# M226A.net
KiCad netlist of a schematic drawn in EAGLE
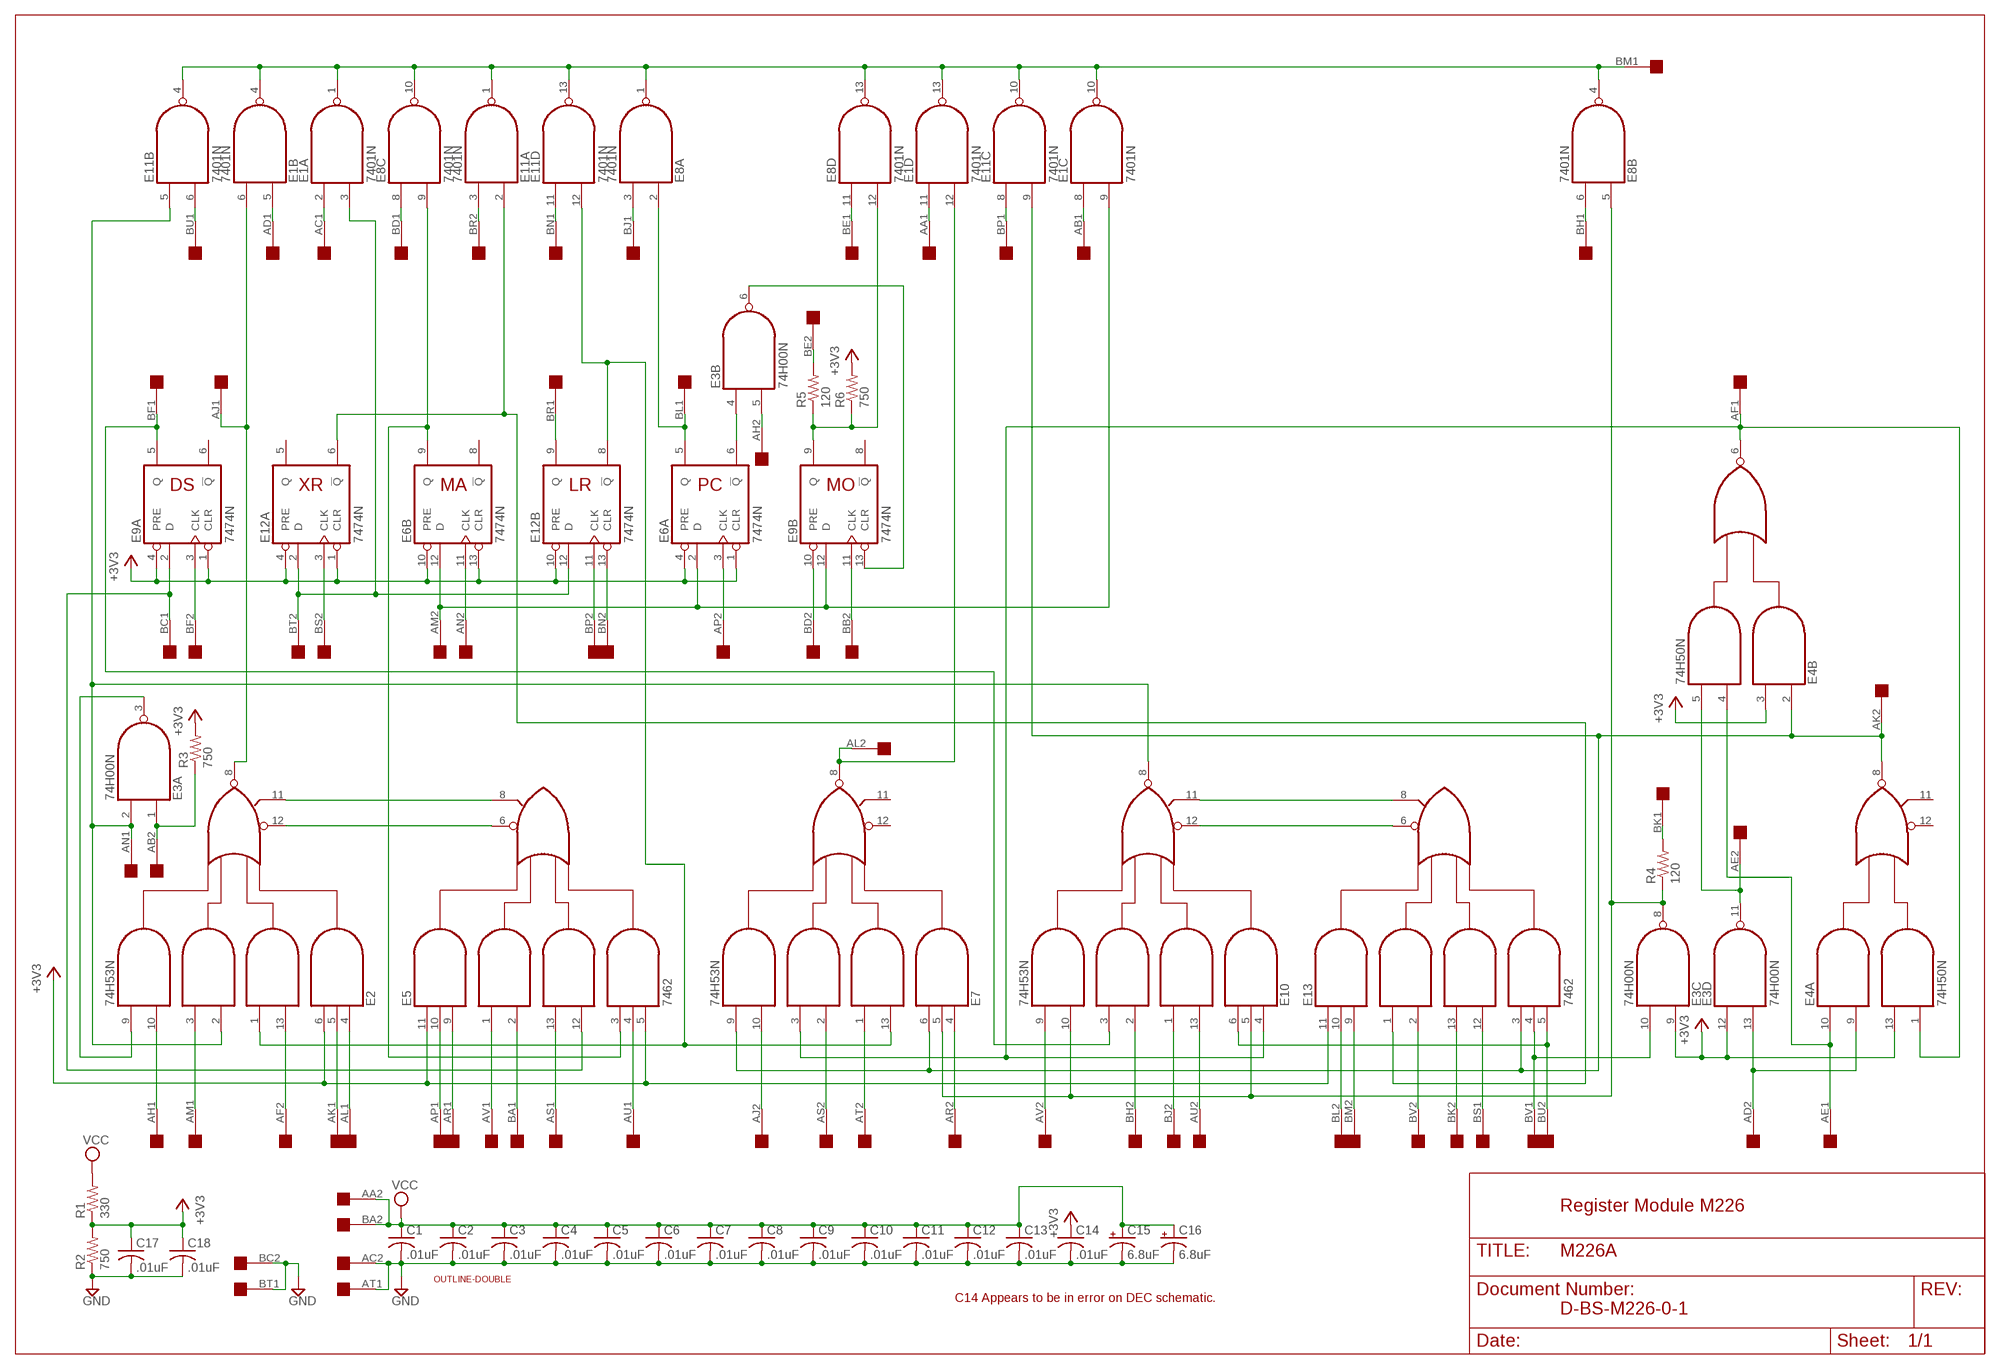
[diagram p0: schematic, sheet 1]

(export (version "E")
  (design (tool "Eeschema 10.0.6"))
  (components
    (comp (ref "C1")
      (value ".01uF")
      (footprint "eagle-import:C050-025X075")
      (libsource (lib "eagle-import") (part "C-US050-025X075"))
    )
    (comp (ref "C2")
      (value ".01uF")
      (footprint "eagle-import:C050-025X075")
      (libsource (lib "eagle-import") (part "C-US050-025X075"))
    )
    (comp (ref "C3")
      (value ".01uF")
      (footprint "eagle-import:C050-025X075")
      (libsource (lib "eagle-import") (part "C-US050-025X075"))
    )
    (comp (ref "C4")
      (value ".01uF")
      (footprint "eagle-import:C050-025X075")
      (libsource (lib "eagle-import") (part "C-US050-025X075"))
    )
    (comp (ref "C5")
      (value ".01uF")
      (footprint "eagle-import:C050-025X075")
      (libsource (lib "eagle-import") (part "C-US050-025X075"))
    )
    (comp (ref "C6")
      (value ".01uF")
      (footprint "eagle-import:C050-025X075")
      (libsource (lib "eagle-import") (part "C-US050-025X075"))
    )
    (comp (ref "C7")
      (value ".01uF")
      (footprint "eagle-import:C050-025X075")
      (libsource (lib "eagle-import") (part "C-US050-025X075"))
    )
    (comp (ref "C8")
      (value ".01uF")
      (footprint "eagle-import:C050-025X075")
      (libsource (lib "eagle-import") (part "C-US050-025X075"))
    )
    (comp (ref "C9")
      (value ".01uF")
      (footprint "eagle-import:C050-025X075")
      (libsource (lib "eagle-import") (part "C-US050-025X075"))
    )
    (comp (ref "C10")
      (value ".01uF")
      (footprint "eagle-import:C050-025X075")
      (libsource (lib "eagle-import") (part "C-US050-025X075"))
    )
    (comp (ref "C11")
      (value ".01uF")
      (footprint "eagle-import:C050-025X075")
      (libsource (lib "eagle-import") (part "C-US050-025X075"))
    )
    (comp (ref "C12")
      (value ".01uF")
      (footprint "eagle-import:C050-025X075")
      (libsource (lib "eagle-import") (part "C-US050-025X075"))
    )
    (comp (ref "C13")
      (value ".01uF")
      (footprint "eagle-import:C050-025X075")
      (libsource (lib "eagle-import") (part "C-US050-025X075"))
    )
    (comp (ref "C14")
      (value ".01uF")
      (footprint "eagle-import:C050-025X075")
      (libsource (lib "eagle-import") (part "C-US050-025X075"))
    )
    (comp (ref "C15")
      (value "6.8uF")
      (footprint "eagle-import:E12-8")
      (libsource (lib "eagle-import") (part "CPOL-USE20-8AXIAL"))
    )
    (comp (ref "C16")
      (value "6.8uF")
      (footprint "eagle-import:E12-8")
      (libsource (lib "eagle-import") (part "CPOL-USE20-8AXIAL"))
    )
    (comp (ref "C17")
      (value ".01uF")
      (footprint "eagle-import:C050-025X075")
      (libsource (lib "eagle-import") (part "C-US050-025X075"))
    )
    (comp (ref "C18")
      (value ".01uF")
      (footprint "eagle-import:C050-025X075")
      (libsource (lib "eagle-import") (part "C-US050-025X075"))
    )
    (comp (ref "E1")
      (value "7401N")
      (footprint "eagle-import:DIL14")
      (libsource (lib "eagle-import") (part "7401NLS"))
    )
    (comp (ref "E2")
      (value "74H53N")
      (footprint "eagle-import:DIL14")
      (libsource (lib "eagle-import") (part "74H53N"))
    )
    (comp (ref "E3")
      (value "74H00N")
      (footprint "eagle-import:DIL14")
      (libsource (lib "eagle-import") (part "7400NS"))
    )
    (comp (ref "E4")
      (value "74H50N")
      (footprint "eagle-import:DIL14")
      (libsource (lib "eagle-import") (part "7450N"))
    )
    (comp (ref "E5")
      (value "7462")
      (footprint "eagle-import:DIL14")
      (libsource (lib "eagle-import") (part "7462"))
    )
    (comp (ref "E6")
      (value "7474N")
      (footprint "eagle-import:DIL14")
      (libsource (lib "eagle-import") (part "7474NS"))
    )
    (comp (ref "E7")
      (value "74H53N")
      (footprint "eagle-import:DIL14")
      (libsource (lib "eagle-import") (part "74H53N"))
    )
    (comp (ref "E8")
      (value "7401N")
      (footprint "eagle-import:DIL14")
      (libsource (lib "eagle-import") (part "7401NLS"))
    )
    (comp (ref "E9")
      (value "7474N")
      (footprint "eagle-import:DIL14")
      (libsource (lib "eagle-import") (part "7474NS"))
    )
    (comp (ref "E10")
      (value "74H53N")
      (footprint "eagle-import:DIL14")
      (libsource (lib "eagle-import") (part "74H53N"))
    )
    (comp (ref "E11")
      (value "7401N")
      (footprint "eagle-import:DIL14")
      (libsource (lib "eagle-import") (part "7401NLS"))
    )
    (comp (ref "E12")
      (value "7474N")
      (footprint "eagle-import:DIL14")
      (libsource (lib "eagle-import") (part "7474NS"))
    )
    (comp (ref "E13")
      (value "7462")
      (footprint "eagle-import:DIL14")
      (libsource (lib "eagle-import") (part "7462"))
    )
    (comp (ref "R1")
      (value "330")
      (footprint "eagle-import:0207_10")
      (libsource (lib "eagle-import") (part "R-US_0207/10"))
    )
    (comp (ref "R2")
      (value "750")
      (footprint "eagle-import:0207_10")
      (libsource (lib "eagle-import") (part "R-US_0207/10"))
    )
    (comp (ref "R3")
      (value "750")
      (footprint "eagle-import:0207_10")
      (libsource (lib "eagle-import") (part "R-US_0207/10"))
    )
    (comp (ref "R4")
      (value "120")
      (footprint "eagle-import:0207_10")
      (libsource (lib "eagle-import") (part "R-US_0207/10"))
    )
    (comp (ref "R5")
      (value "120")
      (footprint "eagle-import:0207_10")
      (libsource (lib "eagle-import") (part "R-US_0207/10"))
    )
    (comp (ref "R6")
      (value "750")
      (footprint "eagle-import:0207_10")
      (libsource (lib "eagle-import") (part "R-US_0207/10"))
    )
    (comp (ref "U$1")
      (value "OUTLINE-DOUBLE")
      (footprint "eagle-import:DOUBLE")
      (libsource (lib "eagle-import") (part "OUTLINE-DOUBLE"))
    )
    (comp (ref "U$3")
      (value "DOUBLE")
      (footprint "eagle-import:EDGE-CON4")
      (libsource (lib "eagle-import") (part "DOUBLE"))
    )
  )
  (nets
    (net (code "1") (name "+3V3") (class "Default")
      (node (ref "C14") (pin "1") (pinfunction "1_1") (pintype "passive"))
      (node (ref "C17") (pin "1") (pinfunction "1_1") (pintype "passive"))
      (node (ref "C18") (pin "1") (pinfunction "1_1") (pintype "passive"))
      (node (ref "E12") (pin "1") (pinfunction "CLR_1") (pintype "input"))
      (node (ref "E12") (pin "10") (pinfunction "PRE_10") (pintype "input"))
      (node (ref "E12") (pin "4") (pinfunction "PRE_4") (pintype "input"))
      (node (ref "E13") (pin "11") (pinfunction "I1_11") (pintype "input"))
      (node (ref "E2") (pin "6") (pinfunction "I2_6") (pintype "input"))
      (node (ref "E3") (pin "12") (pinfunction "I0_12") (pintype "input"))
      (node (ref "E3") (pin "9") (pinfunction "I0_9") (pintype "input"))
      (node (ref "E4") (pin "13") (pinfunction "I3_13") (pintype "input"))
      (node (ref "E4") (pin "3") (pinfunction "I2_3") (pintype "input"))
      (node (ref "E5") (pin "11") (pinfunction "I1_11") (pintype "input"))
      (node (ref "E5") (pin "5") (pinfunction "I10_5") (pintype "input"))
      (node (ref "E6") (pin "1") (pinfunction "CLR_1") (pintype "input"))
      (node (ref "E6") (pin "10") (pinfunction "PRE_10") (pintype "input"))
      (node (ref "E6") (pin "13") (pinfunction "CLR_13") (pintype "input"))
      (node (ref "E6") (pin "4") (pinfunction "PRE_4") (pintype "input"))
      (node (ref "E9") (pin "1") (pinfunction "CLR_1") (pintype "input"))
      (node (ref "E9") (pin "4") (pinfunction "PRE_4") (pintype "input"))
      (node (ref "R1") (pin "1") (pinfunction "1_1") (pintype "passive"))
      (node (ref "R2") (pin "2") (pinfunction "2_2") (pintype "passive"))
      (node (ref "R3") (pin "2") (pinfunction "2_2") (pintype "passive"))
      (node (ref "R6") (pin "2") (pinfunction "2_2") (pintype "passive"))
    )
    (net (code "2") (name "GND") (class "Default")
      (node (ref "C1") (pin "2") (pinfunction "2_2") (pintype "passive"))
      (node (ref "C10") (pin "2") (pinfunction "2_2") (pintype "passive"))
      (node (ref "C11") (pin "2") (pinfunction "2_2") (pintype "passive"))
      (node (ref "C12") (pin "2") (pinfunction "2_2") (pintype "passive"))
      (node (ref "C13") (pin "2") (pinfunction "2_2") (pintype "passive"))
      (node (ref "C14") (pin "2") (pinfunction "2_2") (pintype "passive"))
      (node (ref "C15") (pin "-") (pinfunction "-_-") (pintype "passive"))
      (node (ref "C16") (pin "-") (pinfunction "-_-") (pintype "passive"))
      (node (ref "C17") (pin "2") (pinfunction "2_2") (pintype "passive"))
      (node (ref "C18") (pin "2") (pinfunction "2_2") (pintype "passive"))
      (node (ref "C2") (pin "2") (pinfunction "2_2") (pintype "passive"))
      (node (ref "C3") (pin "2") (pinfunction "2_2") (pintype "passive"))
      (node (ref "C4") (pin "2") (pinfunction "2_2") (pintype "passive"))
      (node (ref "C5") (pin "2") (pinfunction "2_2") (pintype "passive"))
      (node (ref "C6") (pin "2") (pinfunction "2_2") (pintype "passive"))
      (node (ref "C7") (pin "2") (pinfunction "2_2") (pintype "passive"))
      (node (ref "C8") (pin "2") (pinfunction "2_2") (pintype "passive"))
      (node (ref "C9") (pin "2") (pinfunction "2_2") (pintype "passive"))
      (node (ref "R2") (pin "1") (pinfunction "1_1") (pintype "passive"))
      (node (ref "U$3") (pin "AC2") (pinfunction "1_AC2") (pintype "bidirectional"))
      (node (ref "U$3") (pin "AT1") (pinfunction "1_AT1") (pintype "bidirectional"))
      (node (ref "U$3") (pin "BC2") (pinfunction "1_BC2") (pintype "bidirectional"))
      (node (ref "U$3") (pin "BT1") (pinfunction "1_BT1") (pintype "bidirectional"))
    )
    (net (code "3") (name "Net-(E1A-I0)") (class "Default")
      (node (ref "E1") (pin "2") (pinfunction "I0_2") (pintype "input"))
      (node (ref "U$3") (pin "AC1") (pinfunction "1_AC1") (pintype "bidirectional"))
    )
    (net (code "4") (name "Net-(E1B-I0)") (class "Default")
      (node (ref "E1") (pin "5") (pinfunction "I0_5") (pintype "input"))
      (node (ref "U$3") (pin "AD1") (pinfunction "1_AD1") (pintype "bidirectional"))
    )
    (net (code "5") (name "Net-(E1B-I1)") (class "Default")
      (node (ref "E1") (pin "6") (pinfunction "I1_6") (pintype "input"))
      (node (ref "E2") (pin "8") (pinfunction "O_8") (pintype "output"))
      (node (ref "U$3") (pin "AJ1") (pinfunction "1_AJ1") (pintype "bidirectional"))
    )
    (net (code "6") (name "Net-(E1C-I0)") (class "Default")
      (node (ref "E1") (pin "8") (pinfunction "I0_8") (pintype "input"))
      (node (ref "U$3") (pin "AB1") (pinfunction "1_AB1") (pintype "bidirectional"))
    )
    (net (code "7") (name "Net-(E1C-I1)") (class "Default")
      (node (ref "E1") (pin "9") (pinfunction "I1_9") (pintype "input"))
      (node (ref "E6") (pin "12") (pinfunction "D_12") (pintype "input"))
      (node (ref "E6") (pin "2") (pinfunction "D_2") (pintype "input"))
      (node (ref "E9") (pin "12") (pinfunction "D_12") (pintype "input"))
      (node (ref "U$3") (pin "AM2") (pinfunction "1_AM2") (pintype "bidirectional"))
    )
    (net (code "8") (name "Net-(E1D-I0)") (class "Default")
      (node (ref "E1") (pin "11") (pinfunction "I0_11") (pintype "input"))
      (node (ref "U$3") (pin "AA1") (pinfunction "1_AA1") (pintype "bidirectional"))
    )
    (net (code "9") (name "Net-(E1D-I1)") (class "Default")
      (node (ref "E1") (pin "12") (pinfunction "I1_12") (pintype "input"))
      (node (ref "E7") (pin "8") (pinfunction "O_8") (pintype "output"))
      (node (ref "U$3") (pin "AL2") (pinfunction "1_AL2") (pintype "bidirectional"))
    )
    (net (code "10") (name "Net-(E2A-I1)") (class "Default")
      (node (ref "E2") (pin "4") (pinfunction "I1_4") (pintype "input"))
      (node (ref "U$3") (pin "AL1") (pinfunction "1_AL1") (pintype "bidirectional"))
    )
    (net (code "11") (name "Net-(E2A-I3)") (class "Default")
      (node (ref "E2") (pin "13") (pinfunction "I3_13") (pintype "input"))
      (node (ref "U$3") (pin "AF2") (pinfunction "1_AF2") (pintype "bidirectional"))
    )
    (net (code "12") (name "Net-(E2A-I6)") (class "Default")
      (node (ref "E2") (pin "3") (pinfunction "I6_3") (pintype "input"))
      (node (ref "U$3") (pin "AM1") (pinfunction "1_AM1") (pintype "bidirectional"))
    )
    (net (code "13") (name "Net-(E2A-I7)") (class "Default")
      (node (ref "E2") (pin "10") (pinfunction "I7_10") (pintype "input"))
      (node (ref "U$3") (pin "AH1") (pinfunction "1_AH1") (pintype "bidirectional"))
    )
    (net (code "14") (name "Net-(E2A-I8)") (class "Default")
      (node (ref "E2") (pin "9") (pinfunction "I8_9") (pintype "input"))
      (node (ref "E3") (pin "3") (pinfunction "O_3") (pintype "output"))
    )
    (net (code "15") (name "Net-(E2A-I9)") (class "Default")
      (node (ref "E2") (pin "12") (pinfunction "I9_12") (pintype "passive"))
      (node (ref "E5") (pin "6") (pinfunction "E0_6") (pintype "passive"))
    )
    (net (code "16") (name "Net-(E2A-I10)") (class "Default")
      (node (ref "E2") (pin "11") (pinfunction "I10_11") (pintype "passive"))
      (node (ref "E5") (pin "8") (pinfunction "E1_8") (pintype "passive"))
    )
    (net (code "17") (name "Net-(E2A-I11)") (class "Default")
      (node (ref "E2") (pin "5") (pinfunction "I11_5") (pintype "input"))
      (node (ref "U$3") (pin "AK1") (pinfunction "1_AK1") (pintype "bidirectional"))
    )
    (net (code "18") (name "Net-(E3A-I0)") (class "Default")
      (node (ref "E3") (pin "1") (pinfunction "I0_1") (pintype "input"))
      (node (ref "R3") (pin "1") (pinfunction "1_1") (pintype "passive"))
      (node (ref "U$3") (pin "AB2") (pinfunction "1_AB2") (pintype "bidirectional"))
    )
    (net (code "19") (name "Net-(E3B-I0)") (class "Default")
      (node (ref "E3") (pin "4") (pinfunction "I0_4") (pintype "input"))
      (node (ref "E6") (pin "6") (pinfunction "~{Q}_6") (pintype "output"))
    )
    (net (code "20") (name "Net-(E3B-I1)") (class "Default")
      (node (ref "E3") (pin "5") (pinfunction "I1_5") (pintype "input"))
      (node (ref "U$3") (pin "AH2") (pinfunction "1_AH2") (pintype "bidirectional"))
    )
    (net (code "21") (name "Net-(E3B-O)") (class "Default")
      (node (ref "E3") (pin "6") (pinfunction "O_6") (pintype "output"))
      (node (ref "E9") (pin "13") (pinfunction "CLR_13") (pintype "input"))
    )
    (net (code "22") (name "Net-(E3D-I1)") (class "Default")
      (node (ref "E3") (pin "13") (pinfunction "I1_13") (pintype "input"))
      (node (ref "E4") (pin "9") (pinfunction "I2_9") (pintype "input"))
      (node (ref "U$3") (pin "AD2") (pinfunction "1_AD2") (pintype "bidirectional"))
    )
    (net (code "23") (name "Net-(E3D-O)") (class "Default")
      (node (ref "E3") (pin "11") (pinfunction "O_11") (pintype "output"))
      (node (ref "E4") (pin "5") (pinfunction "I4_5") (pintype "input"))
      (node (ref "U$3") (pin "AE2") (pinfunction "1_AE2") (pintype "bidirectional"))
    )
    (net (code "24") (name "Net-(E4A-I1)") (class "Default")
      (node (ref "E4") (pin "10") (pinfunction "I1_10") (pintype "input"))
      (node (ref "E4") (pin "4") (pinfunction "I3_4") (pintype "input"))
      (node (ref "U$3") (pin "AE1") (pinfunction "1_AE1") (pintype "bidirectional"))
    )
    (net (code "25") (name "Net-(E5A-I2)") (class "Default")
      (node (ref "E5") (pin "10") (pinfunction "I2_10") (pintype "input"))
      (node (ref "U$3") (pin "AP1") (pinfunction "1_AP1") (pintype "bidirectional"))
    )
    (net (code "26") (name "Net-(E5A-I3)") (class "Default")
      (node (ref "E5") (pin "9") (pinfunction "I3_9") (pintype "input"))
      (node (ref "U$3") (pin "AR1") (pinfunction "1_AR1") (pintype "bidirectional"))
    )
    (net (code "27") (name "Net-(E5A-I4)") (class "Default")
      (node (ref "E5") (pin "1") (pinfunction "I4_1") (pintype "input"))
      (node (ref "U$3") (pin "AV1") (pinfunction "1_AV1") (pintype "bidirectional"))
    )
    (net (code "28") (name "Net-(E5A-I5)") (class "Default")
      (node (ref "E5") (pin "2") (pinfunction "I5_2") (pintype "input"))
      (node (ref "U$3") (pin "BA1") (pinfunction "1_BA1") (pintype "bidirectional"))
    )
    (net (code "29") (name "Net-(E5A-I6)") (class "Default")
      (node (ref "E5") (pin "13") (pinfunction "I6_13") (pintype "input"))
      (node (ref "U$3") (pin "AS1") (pinfunction "1_AS1") (pintype "bidirectional"))
    )
    (net (code "30") (name "Net-(E5A-I7)") (class "Default")
      (node (ref "E5") (pin "12") (pinfunction "I7_12") (pintype "input"))
      (node (ref "E9") (pin "2") (pinfunction "D_2") (pintype "input"))
      (node (ref "U$3") (pin "BC1") (pinfunction "1_BC1") (pintype "bidirectional"))
    )
    (net (code "31") (name "Net-(E5A-I8)") (class "Default")
      (node (ref "E5") (pin "3") (pinfunction "I8_3") (pintype "input"))
      (node (ref "E6") (pin "9") (pinfunction "Q_9") (pintype "output"))
      (node (ref "E8") (pin "9") (pinfunction "I1_9") (pintype "input"))
    )
    (net (code "32") (name "Net-(E5A-I9)") (class "Default")
      (node (ref "E5") (pin "4") (pinfunction "I9_4") (pintype "input"))
      (node (ref "U$3") (pin "AU1") (pinfunction "1_AU1") (pintype "bidirectional"))
    )
    (net (code "33") (name "Net-(E6A-CLK)") (class "Default")
      (node (ref "E6") (pin "3") (pinfunction "CLK_3") (pintype "input"))
      (node (ref "U$3") (pin "AP2") (pinfunction "1_AP2") (pintype "bidirectional"))
    )
    (net (code "34") (name "Net-(E6A-Q)") (class "Default")
      (node (ref "E6") (pin "5") (pinfunction "Q_5") (pintype "output"))
      (node (ref "E8") (pin "2") (pinfunction "I0_2") (pintype "input"))
      (node (ref "U$3") (pin "BL1") (pinfunction "1_BL1") (pintype "bidirectional"))
    )
    (net (code "35") (name "Net-(E6B-CLK)") (class "Default")
      (node (ref "E6") (pin "11") (pinfunction "CLK_11") (pintype "input"))
      (node (ref "U$3") (pin "AN2") (pinfunction "1_AN2") (pintype "bidirectional"))
    )
    (net (code "36") (name "Net-(E7A-I1)") (class "Default")
      (node (ref "E7") (pin "4") (pinfunction "I1_4") (pintype "input"))
      (node (ref "U$3") (pin "AR2") (pinfunction "1_AR2") (pintype "bidirectional"))
    )
    (net (code "37") (name "Net-(E7A-I4)") (class "Default")
      (node (ref "E7") (pin "1") (pinfunction "I4_1") (pintype "input"))
      (node (ref "U$3") (pin "AT2") (pinfunction "1_AT2") (pintype "bidirectional"))
    )
    (net (code "38") (name "Net-(E7A-I5)") (class "Default")
      (node (ref "E7") (pin "2") (pinfunction "I5_2") (pintype "input"))
      (node (ref "U$3") (pin "AS2") (pinfunction "1_AS2") (pintype "bidirectional"))
    )
    (net (code "39") (name "Net-(E7A-I7)") (class "Default")
      (node (ref "E7") (pin "10") (pinfunction "I7_10") (pintype "input"))
      (node (ref "U$3") (pin "AJ2") (pinfunction "1_AJ2") (pintype "bidirectional"))
    )
    (net (code "40") (name "Net-(E8A-I1)") (class "Default")
      (node (ref "E8") (pin "3") (pinfunction "I1_3") (pintype "input"))
      (node (ref "U$3") (pin "BJ1") (pinfunction "1_BJ1") (pintype "bidirectional"))
    )
    (net (code "41") (name "Net-(E8B-I1)") (class "Default")
      (node (ref "E8") (pin "6") (pinfunction "I1_6") (pintype "input"))
      (node (ref "U$3") (pin "BH1") (pinfunction "1_BH1") (pintype "bidirectional"))
    )
    (net (code "42") (name "Net-(E8C-I0)") (class "Default")
      (node (ref "E8") (pin "8") (pinfunction "I0_8") (pintype "input"))
      (node (ref "U$3") (pin "BD1") (pinfunction "1_BD1") (pintype "bidirectional"))
    )
    (net (code "43") (name "Net-(E8D-I0)") (class "Default")
      (node (ref "E8") (pin "11") (pinfunction "I0_11") (pintype "input"))
      (node (ref "U$3") (pin "BE1") (pinfunction "1_BE1") (pintype "bidirectional"))
    )
    (net (code "44") (name "Net-(E8D-I1)") (class "Default")
      (node (ref "E8") (pin "12") (pinfunction "I1_12") (pintype "input"))
      (node (ref "E9") (pin "9") (pinfunction "Q_9") (pintype "output"))
      (node (ref "R5") (pin "1") (pinfunction "1_1") (pintype "passive"))
      (node (ref "R6") (pin "1") (pinfunction "1_1") (pintype "passive"))
    )
    (net (code "45") (name "Net-(E9A-CLK)") (class "Default")
      (node (ref "E9") (pin "3") (pinfunction "CLK_3") (pintype "input"))
      (node (ref "U$3") (pin "BF2") (pinfunction "1_BF2") (pintype "bidirectional"))
    )
    (net (code "46") (name "Net-(E9B-CLK)") (class "Default")
      (node (ref "E9") (pin "11") (pinfunction "CLK_11") (pintype "input"))
      (node (ref "U$3") (pin "BB2") (pinfunction "1_BB2") (pintype "bidirectional"))
    )
    (net (code "47") (name "Net-(E9B-PRE)") (class "Default")
      (node (ref "E9") (pin "10") (pinfunction "PRE_10") (pintype "input"))
      (node (ref "U$3") (pin "BD2") (pinfunction "1_BD2") (pintype "bidirectional"))
    )
    (net (code "48") (name "Net-(E10A-I1)") (class "Default")
      (node (ref "E10") (pin "4") (pinfunction "I1_4") (pintype "input"))
      (node (ref "E4") (pin "1") (pinfunction "I4_1") (pintype "input"))
      (node (ref "E4") (pin "6") (pinfunction "O_6") (pintype "output"))
      (node (ref "E7") (pin "3") (pinfunction "I6_3") (pintype "input"))
      (node (ref "U$3") (pin "AF1") (pinfunction "1_AF1") (pintype "bidirectional"))
    )
    (net (code "49") (name "Net-(E10A-I2)") (class "Default")
      (node (ref "E10") (pin "6") (pinfunction "I2_6") (pintype "input"))
      (node (ref "E13") (pin "5") (pinfunction "I10_5") (pintype "input"))
      (node (ref "U$3") (pin "BU2") (pinfunction "1_BU2") (pintype "bidirectional"))
    )
    (net (code "50") (name "Net-(E10A-I3)") (class "Default")
      (node (ref "E10") (pin "13") (pinfunction "I3_13") (pintype "input"))
      (node (ref "U$3") (pin "AU2") (pinfunction "1_AU2") (pintype "bidirectional"))
    )
    (net (code "51") (name "Net-(E10A-I4)") (class "Default")
      (node (ref "E10") (pin "1") (pinfunction "I4_1") (pintype "input"))
      (node (ref "U$3") (pin "BJ2") (pinfunction "1_BJ2") (pintype "bidirectional"))
    )
    (net (code "52") (name "Net-(E10A-I5)") (class "Default")
      (node (ref "E10") (pin "2") (pinfunction "I5_2") (pintype "input"))
      (node (ref "U$3") (pin "BH2") (pinfunction "1_BH2") (pintype "bidirectional"))
    )
    (net (code "53") (name "Net-(E10A-I6)") (class "Default")
      (node (ref "E10") (pin "3") (pinfunction "I6_3") (pintype "input"))
      (node (ref "E9") (pin "5") (pinfunction "Q_5") (pintype "output"))
      (node (ref "U$3") (pin "BF1") (pinfunction "1_BF1") (pintype "bidirectional"))
    )
    (net (code "54") (name "Net-(E10A-I8)") (class "Default")
      (node (ref "E10") (pin "9") (pinfunction "I8_9") (pintype "input"))
      (node (ref "U$3") (pin "AV2") (pinfunction "1_AV2") (pintype "bidirectional"))
    )
    (net (code "55") (name "Net-(E10A-I9)") (class "Default")
      (node (ref "E10") (pin "12") (pinfunction "I9_12") (pintype "passive"))
      (node (ref "E13") (pin "6") (pinfunction "E0_6") (pintype "passive"))
    )
    (net (code "56") (name "Net-(E10A-I10)") (class "Default")
      (node (ref "E10") (pin "11") (pinfunction "I10_11") (pintype "passive"))
      (node (ref "E13") (pin "8") (pinfunction "E1_8") (pintype "passive"))
    )
    (net (code "57") (name "Net-(E10A-I11)") (class "Default")
      (node (ref "E10") (pin "10") (pinfunction "I7_10") (pintype "input"))
      (node (ref "E10") (pin "5") (pinfunction "I11_5") (pintype "input"))
      (node (ref "E3") (pin "8") (pinfunction "O_8") (pintype "output"))
      (node (ref "E7") (pin "5") (pinfunction "I11_5") (pintype "input"))
      (node (ref "E8") (pin "5") (pinfunction "I0_5") (pintype "input"))
      (node (ref "R4") (pin "1") (pinfunction "1_1") (pintype "passive"))
    )
    (net (code "58") (name "Net-(E10A-O)") (class "Default")
      (node (ref "E10") (pin "8") (pinfunction "O_8") (pintype "output"))
      (node (ref "E11") (pin "5") (pinfunction "I0_5") (pintype "input"))
      (node (ref "E2") (pin "2") (pinfunction "I5_2") (pintype "input"))
      (node (ref "E3") (pin "2") (pinfunction "I1_2") (pintype "input"))
      (node (ref "U$3") (pin "AN1") (pinfunction "1_AN1") (pintype "bidirectional"))
    )
    (net (code "59") (name "Net-(E11A-I0)") (class "Default")
      (node (ref "E11") (pin "2") (pinfunction "I0_2") (pintype "input"))
      (node (ref "E12") (pin "6") (pinfunction "~{Q}_6") (pintype "output"))
      (node (ref "E13") (pin "1") (pinfunction "I4_1") (pintype "input"))
    )
    (net (code "60") (name "Net-(E11A-I1)") (class "Default")
      (node (ref "E11") (pin "3") (pinfunction "I1_3") (pintype "input"))
      (node (ref "U$3") (pin "BR2") (pinfunction "1_BR2") (pintype "bidirectional"))
    )
    (net (code "61") (name "Net-(E11A-O)") (class "Default")
      (node (ref "E1") (pin "1") (pinfunction "O_1") (pintype "open_collector"))
      (node (ref "E1") (pin "10") (pinfunction "O_10") (pintype "open_collector"))
      (node (ref "E1") (pin "13") (pinfunction "O_13") (pintype "open_collector"))
      (node (ref "E1") (pin "4") (pinfunction "O_4") (pintype "open_collector"))
      (node (ref "E11") (pin "1") (pinfunction "O_1") (pintype "open_collector"))
      (node (ref "E11") (pin "10") (pinfunction "O_10") (pintype "open_collector"))
      (node (ref "E11") (pin "13") (pinfunction "O_13") (pintype "open_collector"))
      (node (ref "E11") (pin "4") (pinfunction "O_4") (pintype "open_collector"))
      (node (ref "E8") (pin "1") (pinfunction "O_1") (pintype "open_collector"))
      (node (ref "E8") (pin "10") (pinfunction "O_10") (pintype "open_collector"))
      (node (ref "E8") (pin "13") (pinfunction "O_13") (pintype "open_collector"))
      (node (ref "E8") (pin "4") (pinfunction "O_4") (pintype "open_collector"))
      (node (ref "U$3") (pin "BM1") (pinfunction "1_BM1") (pintype "bidirectional"))
    )
    (net (code "62") (name "Net-(E11B-I1)") (class "Default")
      (node (ref "E11") (pin "6") (pinfunction "I1_6") (pintype "input"))
      (node (ref "U$3") (pin "BU1") (pinfunction "1_BU1") (pintype "bidirectional"))
    )
    (net (code "63") (name "Net-(E11C-I0)") (class "Default")
      (node (ref "E11") (pin "8") (pinfunction "I0_8") (pintype "input"))
      (node (ref "U$3") (pin "BP1") (pinfunction "1_BP1") (pintype "bidirectional"))
    )
    (net (code "64") (name "Net-(E11C-I1)") (class "Default")
      (node (ref "E11") (pin "9") (pinfunction "I1_9") (pintype "input"))
      (node (ref "E13") (pin "3") (pinfunction "I8_3") (pintype "input"))
      (node (ref "E4") (pin "2") (pinfunction "I1_2") (pintype "input"))
      (node (ref "E4") (pin "8") (pinfunction "O_8") (pintype "output"))
      (node (ref "E7") (pin "6") (pinfunction "I2_6") (pintype "input"))
      (node (ref "E7") (pin "9") (pinfunction "I8_9") (pintype "input"))
      (node (ref "U$3") (pin "AK2") (pinfunction "1_AK2") (pintype "bidirectional"))
    )
    (net (code "65") (name "Net-(E11D-I0)") (class "Default")
      (node (ref "E11") (pin "11") (pinfunction "I0_11") (pintype "input"))
      (node (ref "U$3") (pin "BN1") (pinfunction "1_BN1") (pintype "bidirectional"))
    )
    (net (code "66") (name "Net-(E11D-I1)") (class "Default")
      (node (ref "E11") (pin "12") (pinfunction "I1_12") (pintype "input"))
      (node (ref "E12") (pin "8") (pinfunction "~{Q}_8") (pintype "output"))
      (node (ref "E2") (pin "1") (pinfunction "I4_1") (pintype "input"))
      (node (ref "E7") (pin "13") (pinfunction "I3_13") (pintype "input"))
    )
    (net (code "67") (name "Net-(E12A-CLK)") (class "Default")
      (node (ref "E12") (pin "3") (pinfunction "CLK_3") (pintype "input"))
      (node (ref "U$3") (pin "BS2") (pinfunction "1_BS2") (pintype "bidirectional"))
    )
    (net (code "68") (name "Net-(E12A-D)") (class "Default")
      (node (ref "E1") (pin "3") (pinfunction "I1_3") (pintype "input"))
      (node (ref "E12") (pin "12") (pinfunction "D_12") (pintype "input"))
      (node (ref "E12") (pin "2") (pinfunction "D_2") (pintype "input"))
      (node (ref "U$3") (pin "BT2") (pinfunction "1_BT2") (pintype "bidirectional"))
    )
    (net (code "69") (name "Net-(E12B-CLK)") (class "Default")
      (node (ref "E12") (pin "11") (pinfunction "CLK_11") (pintype "input"))
      (node (ref "U$3") (pin "BP2") (pinfunction "1_BP2") (pintype "bidirectional"))
    )
    (net (code "70") (name "Net-(E12B-CLR)") (class "Default")
      (node (ref "E12") (pin "13") (pinfunction "CLR_13") (pintype "input"))
      (node (ref "U$3") (pin "BN2") (pinfunction "1_BN2") (pintype "bidirectional"))
    )
    (net (code "71") (name "Net-(E12B-Q)") (class "Default")
      (node (ref "E12") (pin "9") (pinfunction "Q_9") (pintype "output"))
      (node (ref "U$3") (pin "BR1") (pinfunction "1_BR1") (pintype "bidirectional"))
    )
    (net (code "72") (name "Net-(E13A-I2)") (class "Default")
      (node (ref "E13") (pin "10") (pinfunction "I2_10") (pintype "input"))
      (node (ref "U$3") (pin "BL2") (pinfunction "1_BL2") (pintype "bidirectional"))
    )
    (net (code "73") (name "Net-(E13A-I3)") (class "Default")
      (node (ref "E13") (pin "9") (pinfunction "I3_9") (pintype "input"))
      (node (ref "U$3") (pin "BM2") (pinfunction "1_BM2") (pintype "bidirectional"))
    )
    (net (code "74") (name "Net-(E13A-I5)") (class "Default")
      (node (ref "E13") (pin "2") (pinfunction "I5_2") (pintype "input"))
      (node (ref "U$3") (pin "BV2") (pinfunction "1_BV2") (pintype "bidirectional"))
    )
    (net (code "75") (name "Net-(E13A-I6)") (class "Default")
      (node (ref "E13") (pin "13") (pinfunction "I6_13") (pintype "input"))
      (node (ref "U$3") (pin "BK2") (pinfunction "1_BK2") (pintype "bidirectional"))
    )
    (net (code "76") (name "Net-(E13A-I7)") (class "Default")
      (node (ref "E13") (pin "12") (pinfunction "I7_12") (pintype "input"))
      (node (ref "U$3") (pin "BS1") (pinfunction "1_BS1") (pintype "bidirectional"))
    )
    (net (code "77") (name "Net-(E13A-I9)") (class "Default")
      (node (ref "E13") (pin "4") (pinfunction "I9_4") (pintype "input"))
      (node (ref "E3") (pin "10") (pinfunction "I1_10") (pintype "input"))
      (node (ref "U$3") (pin "BV1") (pinfunction "1_BV1") (pintype "bidirectional"))
    )
    (net (code "78") (name "Net-(U$3AT-1)") (class "Default")
      (node (ref "R5") (pin "2") (pinfunction "2_2") (pintype "passive"))
      (node (ref "U$3") (pin "BE2") (pinfunction "1_BE2") (pintype "bidirectional"))
    )
    (net (code "79") (name "Net-(U$3BA-1)") (class "Default")
      (node (ref "R4") (pin "2") (pinfunction "2_2") (pintype "passive"))
      (node (ref "U$3") (pin "BK1") (pinfunction "1_BK1") (pintype "bidirectional"))
    )
    (net (code "80") (name "VCC") (class "Default")
      (node (ref "C1") (pin "1") (pinfunction "1_1") (pintype "passive"))
      (node (ref "C10") (pin "1") (pinfunction "1_1") (pintype "passive"))
      (node (ref "C11") (pin "1") (pinfunction "1_1") (pintype "passive"))
      (node (ref "C12") (pin "1") (pinfunction "1_1") (pintype "passive"))
      (node (ref "C13") (pin "1") (pinfunction "1_1") (pintype "passive"))
      (node (ref "C15") (pin "+") (pinfunction "+_+") (pintype "passive"))
      (node (ref "C16") (pin "+") (pinfunction "+_+") (pintype "passive"))
      (node (ref "C2") (pin "1") (pinfunction "1_1") (pintype "passive"))
      (node (ref "C3") (pin "1") (pinfunction "1_1") (pintype "passive"))
      (node (ref "C4") (pin "1") (pinfunction "1_1") (pintype "passive"))
      (node (ref "C5") (pin "1") (pinfunction "1_1") (pintype "passive"))
      (node (ref "C6") (pin "1") (pinfunction "1_1") (pintype "passive"))
      (node (ref "C7") (pin "1") (pinfunction "1_1") (pintype "passive"))
      (node (ref "C8") (pin "1") (pinfunction "1_1") (pintype "passive"))
      (node (ref "C9") (pin "1") (pinfunction "1_1") (pintype "passive"))
      (node (ref "R1") (pin "2") (pinfunction "2_2") (pintype "passive"))
      (node (ref "U$3") (pin "AA2") (pinfunction "1_AA2") (pintype "bidirectional"))
      (node (ref "U$3") (pin "BA2") (pinfunction "1_BA2") (pintype "bidirectional"))
    )
    (net (code "81") (name "unconnected-(E4A-I5-Pad12)") (class "Default")
      (node (ref "E4") (pin "12") (pinfunction "I5_12") (pintype "passive"))
    )
    (net (code "82") (name "unconnected-(E4A-I6-Pad11)") (class "Default")
      (node (ref "E4") (pin "11") (pinfunction "I6_11") (pintype "passive"))
    )
    (net (code "83") (name "unconnected-(E6B-~{Q}-Pad8)") (class "Default")
      (node (ref "E6") (pin "8") (pinfunction "~{Q}_8") (pintype "output"))
    )
    (net (code "84") (name "unconnected-(E7A-I9-Pad12)") (class "Default")
      (node (ref "E7") (pin "12") (pinfunction "I9_12") (pintype "passive"))
    )
    (net (code "85") (name "unconnected-(E7A-I10-Pad11)") (class "Default")
      (node (ref "E7") (pin "11") (pinfunction "I10_11") (pintype "passive"))
    )
    (net (code "86") (name "unconnected-(E9A-~{Q}-Pad6)") (class "Default")
      (node (ref "E9") (pin "6") (pinfunction "~{Q}_6") (pintype "output"))
    )
    (net (code "87") (name "unconnected-(E9B-~{Q}-Pad8)") (class "Default")
      (node (ref "E9") (pin "8") (pinfunction "~{Q}_8") (pintype "output"))
    )
    (net (code "88") (name "unconnected-(E12A-Q-Pad5)") (class "Default")
      (node (ref "E12") (pin "5") (pinfunction "Q_5") (pintype "output"))
    )
  )
)
